# bldc.net
KiCad netlist of a schematic drawn in EAGLE
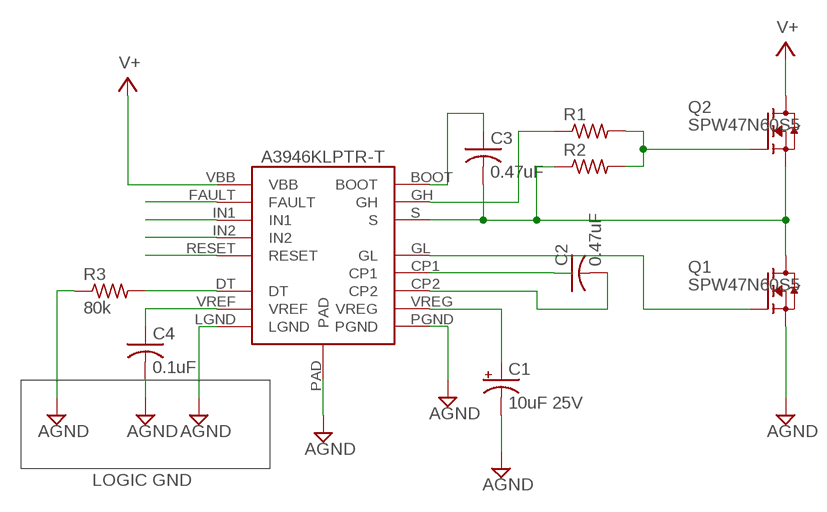
[diagram p0: schematic, sheet 1]

(export (version "E")
  (design (tool "Eeschema 10.0.6"))
  (components
    (comp (ref "C1")
      (value "10uF 25V")
      (footprint "eagle-import:175TMP-0808")
      (libsource (lib "eagle-import") (part "CPOL-US175TMP-0808"))
    )
    (comp (ref "C2")
      (value "0.47uF")
      (footprint "eagle-import:C0805")
      (libsource (lib "eagle-import") (part "C-USC0805"))
    )
    (comp (ref "C3")
      (value "0.47uF")
      (footprint "eagle-import:C050-030X075")
      (libsource (lib "eagle-import") (part "C-US050-030X075"))
    )
    (comp (ref "C4")
      (value "0.1uF")
      (footprint "eagle-import:C0805")
      (libsource (lib "eagle-import") (part "C-USC0805"))
    )
    (comp (ref "Q1")
      (value "SPW47N60S5")
      (footprint "eagle-import:P-TO247")
      (libsource (lib "eagle-import") (part "SPW47N60S5"))
    )
    (comp (ref "Q2")
      (value "SPW47N60S5")
      (footprint "eagle-import:P-TO247")
      (libsource (lib "eagle-import") (part "SPW47N60S5"))
    )
    (comp (ref "R1")
      (value "R-US_R0805")
      (footprint "eagle-import:R0805")
      (libsource (lib "eagle-import") (part "R-US_R0805"))
    )
    (comp (ref "R2")
      (value "R-US_R0805")
      (footprint "eagle-import:R0805")
      (libsource (lib "eagle-import") (part "R-US_R0805"))
    )
    (comp (ref "R3")
      (value "80k")
      (footprint "eagle-import:R0805")
      (libsource (lib "eagle-import") (part "R-US_R0805"))
    )
    (comp (ref "U$1")
      (value "A3946KLPTR-T")
      (footprint "eagle-import:SOP65P640X120-17T300")
      (libsource (lib "eagle-import") (part "A3946KLPTR-T"))
    )
  )
  (nets
    (net (code "1") (name "AGND") (class "Default")
      (node (ref "C1") (pin "-") (pinfunction "-_-") (pintype "passive"))
      (node (ref "C4") (pin "2") (pinfunction "2_2") (pintype "passive"))
      (node (ref "Q1") (pin "3") (pinfunction "S_3") (pintype "passive"))
      (node (ref "R3") (pin "1") (pinfunction "1_1") (pintype "passive"))
      (node (ref "U$1") (pin "LGND") (pinfunction "LGND_LGND") (pintype "bidirectional"))
      (node (ref "U$1") (pin "PAD") (pinfunction "PAD_PAD") (pintype "bidirectional"))
      (node (ref "U$1") (pin "PGND") (pinfunction "PGND_PGND") (pintype "bidirectional"))
    )
    (net (code "2") (name "Net-(C1-Pad+)") (class "Default")
      (node (ref "C1") (pin "+") (pinfunction "+_+") (pintype "passive"))
      (node (ref "U$1") (pin "VREG") (pinfunction "VREG_VREG") (pintype "bidirectional"))
    )
    (net (code "3") (name "Net-(C2-Pad1)") (class "Default")
      (node (ref "C2") (pin "1") (pinfunction "1_1") (pintype "passive"))
      (node (ref "U$1") (pin "CP1") (pinfunction "CP1_CP1") (pintype "bidirectional"))
    )
    (net (code "4") (name "Net-(C2-Pad2)") (class "Default")
      (node (ref "C2") (pin "2") (pinfunction "2_2") (pintype "passive"))
      (node (ref "U$1") (pin "CP2") (pinfunction "CP2_CP2") (pintype "bidirectional"))
    )
    (net (code "5") (name "Net-(C3-Pad1)") (class "Default")
      (node (ref "C3") (pin "1") (pinfunction "1_1") (pintype "passive"))
      (node (ref "U$1") (pin "BOOT") (pinfunction "BOOT_BOOT") (pintype "bidirectional"))
    )
    (net (code "6") (name "Net-(C4-Pad1)") (class "Default")
      (node (ref "C4") (pin "1") (pinfunction "1_1") (pintype "passive"))
      (node (ref "U$1") (pin "VREF") (pinfunction "VREF_VREF") (pintype "bidirectional"))
    )
    (net (code "7") (name "Net-(Q1-D)") (class "Default")
      (node (ref "C3") (pin "2") (pinfunction "2_2") (pintype "passive"))
      (node (ref "Q1") (pin "2") (pinfunction "D_2") (pintype "passive"))
      (node (ref "Q2") (pin "3") (pinfunction "S_3") (pintype "passive"))
      (node (ref "R2") (pin "1") (pinfunction "1_1") (pintype "passive"))
      (node (ref "U$1") (pin "S") (pinfunction "S_S") (pintype "bidirectional"))
    )
    (net (code "8") (name "Net-(Q1-G)") (class "Default")
      (node (ref "Q1") (pin "1") (pinfunction "G_1") (pintype "passive"))
      (node (ref "U$1") (pin "GL") (pinfunction "GL_GL") (pintype "bidirectional"))
    )
    (net (code "9") (name "Net-(Q2-G)") (class "Default")
      (node (ref "Q2") (pin "1") (pinfunction "G_1") (pintype "passive"))
      (node (ref "R1") (pin "2") (pinfunction "2_2") (pintype "passive"))
      (node (ref "R2") (pin "2") (pinfunction "2_2") (pintype "passive"))
    )
    (net (code "10") (name "Net-(R1-Pad1)") (class "Default")
      (node (ref "R1") (pin "1") (pinfunction "1_1") (pintype "passive"))
      (node (ref "U$1") (pin "GH") (pinfunction "GH_GH") (pintype "bidirectional"))
    )
    (net (code "11") (name "Net-(R3-Pad2)") (class "Default")
      (node (ref "R3") (pin "2") (pinfunction "2_2") (pintype "passive"))
      (node (ref "U$1") (pin "DT") (pinfunction "DT_DT") (pintype "bidirectional"))
    )
    (net (code "12") (name "V+") (class "Default")
      (node (ref "Q2") (pin "2") (pinfunction "D_2") (pintype "passive"))
      (node (ref "U$1") (pin "VBB") (pinfunction "VBB_VBB") (pintype "bidirectional"))
    )
    (net (code "13") (name "unconnected-(U$1-PadFAULT)") (class "Default")
      (node (ref "U$1") (pin "FAULT") (pinfunction "FAULT_FAULT") (pintype "bidirectional"))
    )
    (net (code "14") (name "unconnected-(U$1-PadIN1)") (class "Default")
      (node (ref "U$1") (pin "IN1") (pinfunction "IN1_IN1") (pintype "bidirectional"))
    )
    (net (code "15") (name "unconnected-(U$1-PadIN2)") (class "Default")
      (node (ref "U$1") (pin "IN2") (pinfunction "IN2_IN2") (pintype "bidirectional"))
    )
    (net (code "16") (name "unconnected-(U$1-PadRESET)") (class "Default")
      (node (ref "U$1") (pin "RESET") (pinfunction "RESET_RESET") (pintype "bidirectional"))
    )
  )
)
